# SIDEPANELV5.net
KiCad netlist of a schematic drawn in EAGLE
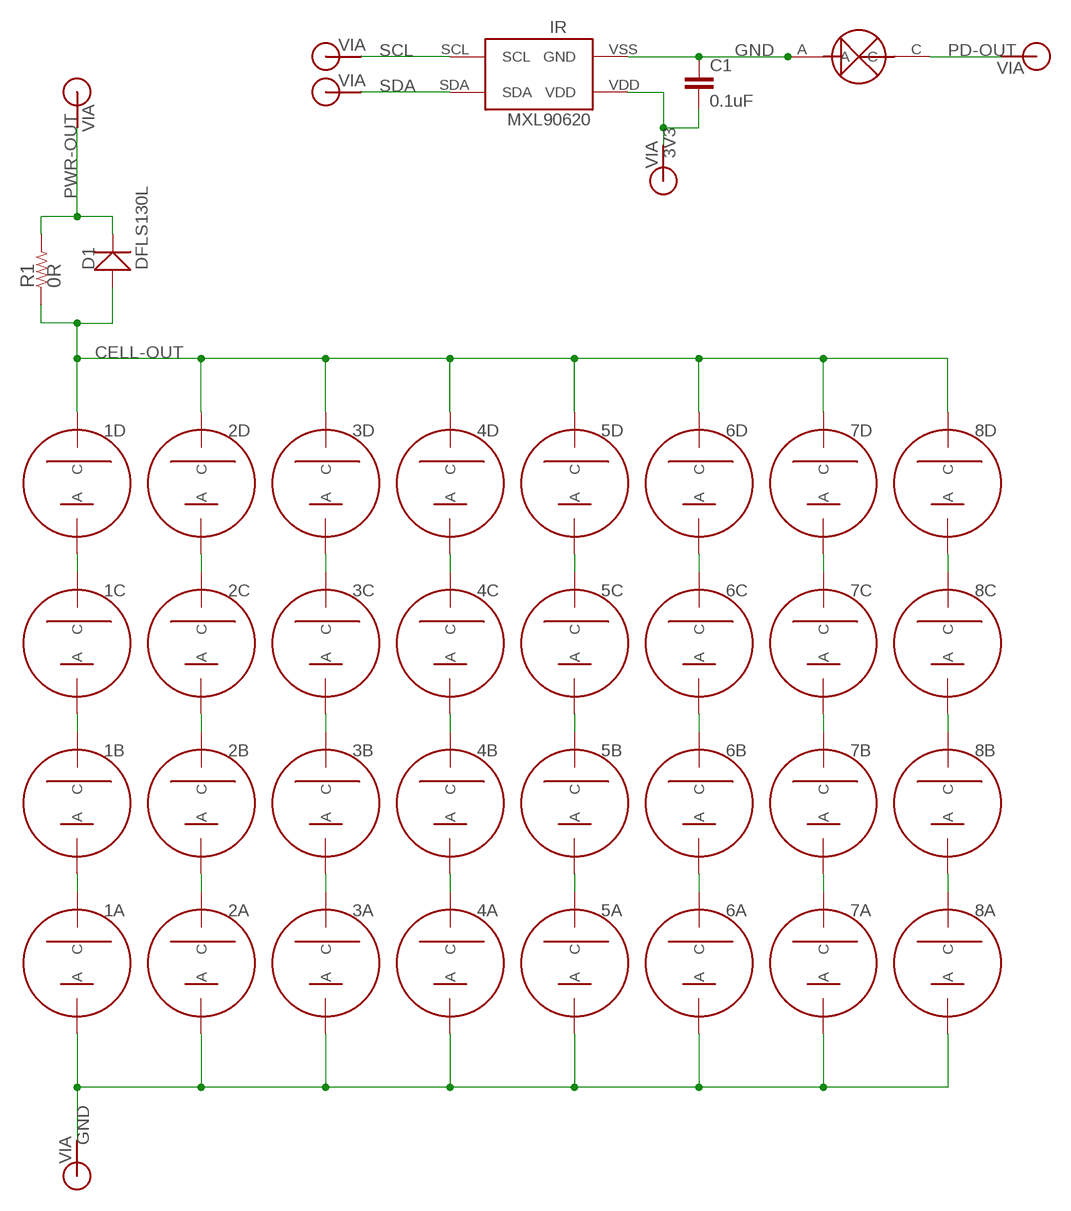
[diagram p0: schematic, sheet 1]

(export (version "E")
  (design (tool "Eeschema 10.0.6"))
  (components
    (comp (ref "1A")
      (value "SOLARCELLV3")
      (footprint "eagle-import:TRISOLX-V3")
      (libsource (lib "eagle-import") (part "SOLARCELLV3"))
    )
    (comp (ref "1B")
      (value "SOLARCELLV3")
      (footprint "eagle-import:TRISOLX-V3")
      (libsource (lib "eagle-import") (part "SOLARCELLV3"))
    )
    (comp (ref "1C")
      (value "SOLARCELLV3")
      (footprint "eagle-import:TRISOLX-V3")
      (libsource (lib "eagle-import") (part "SOLARCELLV3"))
    )
    (comp (ref "1D")
      (value "SOLARCELLV3")
      (footprint "eagle-import:TRISOLX-V3")
      (libsource (lib "eagle-import") (part "SOLARCELLV3"))
    )
    (comp (ref "2A")
      (value "SOLARCELLV3")
      (footprint "eagle-import:TRISOLX-V3")
      (libsource (lib "eagle-import") (part "SOLARCELLV3"))
    )
    (comp (ref "2B")
      (value "SOLARCELLV3")
      (footprint "eagle-import:TRISOLX-V3")
      (libsource (lib "eagle-import") (part "SOLARCELLV3"))
    )
    (comp (ref "2C")
      (value "SOLARCELLV3")
      (footprint "eagle-import:TRISOLX-V3")
      (libsource (lib "eagle-import") (part "SOLARCELLV3"))
    )
    (comp (ref "2D")
      (value "SOLARCELLV3")
      (footprint "eagle-import:TRISOLX-V3")
      (libsource (lib "eagle-import") (part "SOLARCELLV3"))
    )
    (comp (ref "3A")
      (value "SOLARCELLV3")
      (footprint "eagle-import:TRISOLX-V3")
      (libsource (lib "eagle-import") (part "SOLARCELLV3"))
    )
    (comp (ref "3B")
      (value "SOLARCELLV3")
      (footprint "eagle-import:TRISOLX-V3")
      (libsource (lib "eagle-import") (part "SOLARCELLV3"))
    )
    (comp (ref "3C")
      (value "SOLARCELLV3")
      (footprint "eagle-import:TRISOLX-V3")
      (libsource (lib "eagle-import") (part "SOLARCELLV3"))
    )
    (comp (ref "3D")
      (value "SOLARCELLV3")
      (footprint "eagle-import:TRISOLX-V3")
      (libsource (lib "eagle-import") (part "SOLARCELLV3"))
    )
    (comp (ref "3V3")
      (value "VIA60MIL-SQ")
      (footprint "eagle-import:VIA-60MIL-SQ")
      (libsource (lib "eagle-import") (part "VIA60MIL-SQ"))
    )
    (comp (ref "4A")
      (value "SOLARCELLV3")
      (footprint "eagle-import:TRISOLX-V3")
      (libsource (lib "eagle-import") (part "SOLARCELLV3"))
    )
    (comp (ref "4B")
      (value "SOLARCELLV3")
      (footprint "eagle-import:TRISOLX-V3")
      (libsource (lib "eagle-import") (part "SOLARCELLV3"))
    )
    (comp (ref "4C")
      (value "SOLARCELLV3")
      (footprint "eagle-import:TRISOLX-V3")
      (libsource (lib "eagle-import") (part "SOLARCELLV3"))
    )
    (comp (ref "4D")
      (value "SOLARCELLV3")
      (footprint "eagle-import:TRISOLX-V3")
      (libsource (lib "eagle-import") (part "SOLARCELLV3"))
    )
    (comp (ref "5A")
      (value "SOLARCELLV3")
      (footprint "eagle-import:TRISOLX-V3")
      (libsource (lib "eagle-import") (part "SOLARCELLV3"))
    )
    (comp (ref "5B")
      (value "SOLARCELLV3")
      (footprint "eagle-import:TRISOLX-V3")
      (libsource (lib "eagle-import") (part "SOLARCELLV3"))
    )
    (comp (ref "5C")
      (value "SOLARCELLV3")
      (footprint "eagle-import:TRISOLX-V3")
      (libsource (lib "eagle-import") (part "SOLARCELLV3"))
    )
    (comp (ref "5D")
      (value "SOLARCELLV3")
      (footprint "eagle-import:TRISOLX-V3")
      (libsource (lib "eagle-import") (part "SOLARCELLV3"))
    )
    (comp (ref "6A")
      (value "SOLARCELLV3")
      (footprint "eagle-import:TRISOLX-V3")
      (libsource (lib "eagle-import") (part "SOLARCELLV3"))
    )
    (comp (ref "6B")
      (value "SOLARCELLV3")
      (footprint "eagle-import:TRISOLX-V3")
      (libsource (lib "eagle-import") (part "SOLARCELLV3"))
    )
    (comp (ref "6C")
      (value "SOLARCELLV3")
      (footprint "eagle-import:TRISOLX-V3")
      (libsource (lib "eagle-import") (part "SOLARCELLV3"))
    )
    (comp (ref "6D")
      (value "SOLARCELLV3")
      (footprint "eagle-import:TRISOLX-V3")
      (libsource (lib "eagle-import") (part "SOLARCELLV3"))
    )
    (comp (ref "7A")
      (value "SOLARCELLV3")
      (footprint "eagle-import:TRISOLX-V3")
      (libsource (lib "eagle-import") (part "SOLARCELLV3"))
    )
    (comp (ref "7B")
      (value "SOLARCELLV3")
      (footprint "eagle-import:TRISOLX-V3")
      (libsource (lib "eagle-import") (part "SOLARCELLV3"))
    )
    (comp (ref "7C")
      (value "SOLARCELLV3")
      (footprint "eagle-import:TRISOLX-V3")
      (libsource (lib "eagle-import") (part "SOLARCELLV3"))
    )
    (comp (ref "7D")
      (value "SOLARCELLV3")
      (footprint "eagle-import:TRISOLX-V3")
      (libsource (lib "eagle-import") (part "SOLARCELLV3"))
    )
    (comp (ref "8A")
      (value "SOLARCELLV3")
      (footprint "eagle-import:TRISOLX-V3")
      (libsource (lib "eagle-import") (part "SOLARCELLV3"))
    )
    (comp (ref "8B")
      (value "SOLARCELLV3")
      (footprint "eagle-import:TRISOLX-V3")
      (libsource (lib "eagle-import") (part "SOLARCELLV3"))
    )
    (comp (ref "8C")
      (value "SOLARCELLV3")
      (footprint "eagle-import:TRISOLX-V3")
      (libsource (lib "eagle-import") (part "SOLARCELLV3"))
    )
    (comp (ref "8D")
      (value "SOLARCELLV3")
      (footprint "eagle-import:TRISOLX-V3")
      (libsource (lib "eagle-import") (part "SOLARCELLV3"))
    )
    (comp (ref "C1")
      (value "0.1uF")
      (footprint "eagle-import:0805")
      (libsource (lib "eagle-import") (part "CAP0805"))
    )
    (comp (ref "D1")
      (value "DFLS130L")
      (footprint "eagle-import:PWRDI-123")
      (libsource (lib "eagle-import") (part "DFLS130L"))
    )
    (comp (ref "GND")
      (value "VIA60MIL-SQ")
      (footprint "eagle-import:VIA-60MIL-SQ")
      (libsource (lib "eagle-import") (part "VIA60MIL-SQ"))
    )
    (comp (ref "IR")
      (value "MXL90620")
      (footprint "eagle-import:MXL90620")
      (libsource (lib "eagle-import") (part "MXL90620"))
    )
    (comp (ref "PD")
      (value "PHOTODETECTOR")
      (footprint "eagle-import:PHOTODECTORDEVICE2")
      (libsource (lib "eagle-import") (part "PHOTODETECTOR"))
    )
    (comp (ref "PD-OUT")
      (value "VIA60MIL-SQ")
      (footprint "eagle-import:VIA-60MIL-SQ")
      (libsource (lib "eagle-import") (part "VIA60MIL-SQ"))
    )
    (comp (ref "PWR-OUT")
      (value "VIA60MIL-SQ")
      (footprint "eagle-import:VIA-60MIL-SQ")
      (libsource (lib "eagle-import") (part "VIA60MIL-SQ"))
    )
    (comp (ref "R1")
      (value "0R")
      (footprint "eagle-import:1210")
      (libsource (lib "eagle-import") (part "RES1210"))
    )
    (comp (ref "SCL")
      (value "VIA60MIL-SQ")
      (footprint "eagle-import:VIA-60MIL-SQ")
      (libsource (lib "eagle-import") (part "VIA60MIL-SQ"))
    )
    (comp (ref "SDA")
      (value "VIA60MIL-SQ")
      (footprint "eagle-import:VIA-60MIL-SQ")
      (libsource (lib "eagle-import") (part "VIA60MIL-SQ"))
    )
  )
  (nets
    (net (code "1") (name "/3V3") (class "Default")
      (node (ref "3V3") (pin "P$1") (pinfunction "P$1_P$1") (pintype "bidirectional"))
      (node (ref "C1") (pin "2") (pinfunction "2_2") (pintype "passive"))
      (node (ref "IR") (pin "VDD") (pinfunction "VDD_VDD") (pintype "bidirectional"))
    )
    (net (code "2") (name "/CELL-OUT") (class "Default")
      (node (ref "1D") (pin "CATHODE") (pinfunction "C_CATHODE") (pintype "bidirectional"))
      (node (ref "2D") (pin "CATHODE") (pinfunction "C_CATHODE") (pintype "bidirectional"))
      (node (ref "3D") (pin "CATHODE") (pinfunction "C_CATHODE") (pintype "bidirectional"))
      (node (ref "4D") (pin "CATHODE") (pinfunction "C_CATHODE") (pintype "bidirectional"))
      (node (ref "5D") (pin "CATHODE") (pinfunction "C_CATHODE") (pintype "bidirectional"))
      (node (ref "6D") (pin "CATHODE") (pinfunction "C_CATHODE") (pintype "bidirectional"))
      (node (ref "7D") (pin "CATHODE") (pinfunction "C_CATHODE") (pintype "bidirectional"))
      (node (ref "8D") (pin "CATHODE") (pinfunction "C_CATHODE") (pintype "bidirectional"))
      (node (ref "D1") (pin "A") (pinfunction "A_A") (pintype "bidirectional"))
      (node (ref "R1") (pin "P$1") (pinfunction "1_P$1") (pintype "passive"))
    )
    (net (code "3") (name "/GND") (class "Default")
      (node (ref "1A") (pin "ANODE") (pinfunction "A_ANODE") (pintype "bidirectional"))
      (node (ref "2A") (pin "ANODE") (pinfunction "A_ANODE") (pintype "bidirectional"))
      (node (ref "3A") (pin "ANODE") (pinfunction "A_ANODE") (pintype "bidirectional"))
      (node (ref "4A") (pin "ANODE") (pinfunction "A_ANODE") (pintype "bidirectional"))
      (node (ref "5A") (pin "ANODE") (pinfunction "A_ANODE") (pintype "bidirectional"))
      (node (ref "6A") (pin "ANODE") (pinfunction "A_ANODE") (pintype "bidirectional"))
      (node (ref "7A") (pin "ANODE") (pinfunction "A_ANODE") (pintype "bidirectional"))
      (node (ref "8A") (pin "ANODE") (pinfunction "A_ANODE") (pintype "bidirectional"))
      (node (ref "C1") (pin "1") (pinfunction "1_1") (pintype "passive"))
      (node (ref "GND") (pin "P$1") (pinfunction "P$1_P$1") (pintype "bidirectional"))
      (node (ref "IR") (pin "VSS") (pinfunction "GND_VSS") (pintype "bidirectional"))
      (node (ref "PD") (pin "A") (pinfunction "A_A") (pintype "bidirectional"))
    )
    (net (code "4") (name "/PD-OUT") (class "Default")
      (node (ref "PD") (pin "C") (pinfunction "C_C") (pintype "bidirectional"))
      (node (ref "PD-OUT") (pin "P$1") (pinfunction "P$1_P$1") (pintype "bidirectional"))
    )
    (net (code "5") (name "/PWR-OUT") (class "Default")
      (node (ref "D1") (pin "C") (pinfunction "C_C") (pintype "bidirectional"))
      (node (ref "PWR-OUT") (pin "P$1") (pinfunction "P$1_P$1") (pintype "bidirectional"))
      (node (ref "R1") (pin "P$2") (pinfunction "2_P$2") (pintype "passive"))
    )
    (net (code "6") (name "/SCL") (class "Default")
      (node (ref "IR") (pin "SCL") (pinfunction "SCL_SCL") (pintype "bidirectional"))
      (node (ref "SCL") (pin "P$1") (pinfunction "P$1_P$1") (pintype "bidirectional"))
    )
    (net (code "7") (name "/SDA") (class "Default")
      (node (ref "IR") (pin "SDA") (pinfunction "SDA_SDA") (pintype "bidirectional"))
      (node (ref "SDA") (pin "P$1") (pinfunction "P$1_P$1") (pintype "bidirectional"))
    )
    (net (code "8") (name "Net-(1A-C)") (class "Default")
      (node (ref "1A") (pin "CATHODE") (pinfunction "C_CATHODE") (pintype "bidirectional"))
      (node (ref "1B") (pin "ANODE") (pinfunction "A_ANODE") (pintype "bidirectional"))
    )
    (net (code "9") (name "Net-(1B-C)") (class "Default")
      (node (ref "1B") (pin "CATHODE") (pinfunction "C_CATHODE") (pintype "bidirectional"))
      (node (ref "1C") (pin "ANODE") (pinfunction "A_ANODE") (pintype "bidirectional"))
    )
    (net (code "10") (name "Net-(1C-C)") (class "Default")
      (node (ref "1C") (pin "CATHODE") (pinfunction "C_CATHODE") (pintype "bidirectional"))
      (node (ref "1D") (pin "ANODE") (pinfunction "A_ANODE") (pintype "bidirectional"))
    )
    (net (code "11") (name "Net-(2A-C)") (class "Default")
      (node (ref "2A") (pin "CATHODE") (pinfunction "C_CATHODE") (pintype "bidirectional"))
      (node (ref "2B") (pin "ANODE") (pinfunction "A_ANODE") (pintype "bidirectional"))
    )
    (net (code "12") (name "Net-(2B-C)") (class "Default")
      (node (ref "2B") (pin "CATHODE") (pinfunction "C_CATHODE") (pintype "bidirectional"))
      (node (ref "2C") (pin "ANODE") (pinfunction "A_ANODE") (pintype "bidirectional"))
    )
    (net (code "13") (name "Net-(2C-C)") (class "Default")
      (node (ref "2C") (pin "CATHODE") (pinfunction "C_CATHODE") (pintype "bidirectional"))
      (node (ref "2D") (pin "ANODE") (pinfunction "A_ANODE") (pintype "bidirectional"))
    )
    (net (code "14") (name "Net-(3A-C)") (class "Default")
      (node (ref "3A") (pin "CATHODE") (pinfunction "C_CATHODE") (pintype "bidirectional"))
      (node (ref "3B") (pin "ANODE") (pinfunction "A_ANODE") (pintype "bidirectional"))
    )
    (net (code "15") (name "Net-(3B-C)") (class "Default")
      (node (ref "3B") (pin "CATHODE") (pinfunction "C_CATHODE") (pintype "bidirectional"))
      (node (ref "3C") (pin "ANODE") (pinfunction "A_ANODE") (pintype "bidirectional"))
    )
    (net (code "16") (name "Net-(3C-C)") (class "Default")
      (node (ref "3C") (pin "CATHODE") (pinfunction "C_CATHODE") (pintype "bidirectional"))
      (node (ref "3D") (pin "ANODE") (pinfunction "A_ANODE") (pintype "bidirectional"))
    )
    (net (code "17") (name "Net-(4A-C)") (class "Default")
      (node (ref "4A") (pin "CATHODE") (pinfunction "C_CATHODE") (pintype "bidirectional"))
      (node (ref "4B") (pin "ANODE") (pinfunction "A_ANODE") (pintype "bidirectional"))
    )
    (net (code "18") (name "Net-(4B-C)") (class "Default")
      (node (ref "4B") (pin "CATHODE") (pinfunction "C_CATHODE") (pintype "bidirectional"))
      (node (ref "4C") (pin "ANODE") (pinfunction "A_ANODE") (pintype "bidirectional"))
    )
    (net (code "19") (name "Net-(4C-C)") (class "Default")
      (node (ref "4C") (pin "CATHODE") (pinfunction "C_CATHODE") (pintype "bidirectional"))
      (node (ref "4D") (pin "ANODE") (pinfunction "A_ANODE") (pintype "bidirectional"))
    )
    (net (code "20") (name "Net-(5A-C)") (class "Default")
      (node (ref "5A") (pin "CATHODE") (pinfunction "C_CATHODE") (pintype "bidirectional"))
      (node (ref "5B") (pin "ANODE") (pinfunction "A_ANODE") (pintype "bidirectional"))
    )
    (net (code "21") (name "Net-(5B-C)") (class "Default")
      (node (ref "5B") (pin "CATHODE") (pinfunction "C_CATHODE") (pintype "bidirectional"))
      (node (ref "5C") (pin "ANODE") (pinfunction "A_ANODE") (pintype "bidirectional"))
    )
    (net (code "22") (name "Net-(5C-C)") (class "Default")
      (node (ref "5C") (pin "CATHODE") (pinfunction "C_CATHODE") (pintype "bidirectional"))
      (node (ref "5D") (pin "ANODE") (pinfunction "A_ANODE") (pintype "bidirectional"))
    )
    (net (code "23") (name "Net-(6A-C)") (class "Default")
      (node (ref "6A") (pin "CATHODE") (pinfunction "C_CATHODE") (pintype "bidirectional"))
      (node (ref "6B") (pin "ANODE") (pinfunction "A_ANODE") (pintype "bidirectional"))
    )
    (net (code "24") (name "Net-(6B-C)") (class "Default")
      (node (ref "6B") (pin "CATHODE") (pinfunction "C_CATHODE") (pintype "bidirectional"))
      (node (ref "6C") (pin "ANODE") (pinfunction "A_ANODE") (pintype "bidirectional"))
    )
    (net (code "25") (name "Net-(6C-C)") (class "Default")
      (node (ref "6C") (pin "CATHODE") (pinfunction "C_CATHODE") (pintype "bidirectional"))
      (node (ref "6D") (pin "ANODE") (pinfunction "A_ANODE") (pintype "bidirectional"))
    )
    (net (code "26") (name "Net-(7A-C)") (class "Default")
      (node (ref "7A") (pin "CATHODE") (pinfunction "C_CATHODE") (pintype "bidirectional"))
      (node (ref "7B") (pin "ANODE") (pinfunction "A_ANODE") (pintype "bidirectional"))
    )
    (net (code "27") (name "Net-(7B-C)") (class "Default")
      (node (ref "7B") (pin "CATHODE") (pinfunction "C_CATHODE") (pintype "bidirectional"))
      (node (ref "7C") (pin "ANODE") (pinfunction "A_ANODE") (pintype "bidirectional"))
    )
    (net (code "28") (name "Net-(7C-C)") (class "Default")
      (node (ref "7C") (pin "CATHODE") (pinfunction "C_CATHODE") (pintype "bidirectional"))
      (node (ref "7D") (pin "ANODE") (pinfunction "A_ANODE") (pintype "bidirectional"))
    )
    (net (code "29") (name "Net-(8A-C)") (class "Default")
      (node (ref "8A") (pin "CATHODE") (pinfunction "C_CATHODE") (pintype "bidirectional"))
      (node (ref "8B") (pin "ANODE") (pinfunction "A_ANODE") (pintype "bidirectional"))
    )
    (net (code "30") (name "Net-(8B-C)") (class "Default")
      (node (ref "8B") (pin "CATHODE") (pinfunction "C_CATHODE") (pintype "bidirectional"))
      (node (ref "8C") (pin "ANODE") (pinfunction "A_ANODE") (pintype "bidirectional"))
    )
    (net (code "31") (name "Net-(8C-C)") (class "Default")
      (node (ref "8C") (pin "CATHODE") (pinfunction "C_CATHODE") (pintype "bidirectional"))
      (node (ref "8D") (pin "ANODE") (pinfunction "A_ANODE") (pintype "bidirectional"))
    )
  )
)
